# pulse_generator.net
KiCad netlist of a schematic drawn in EAGLE
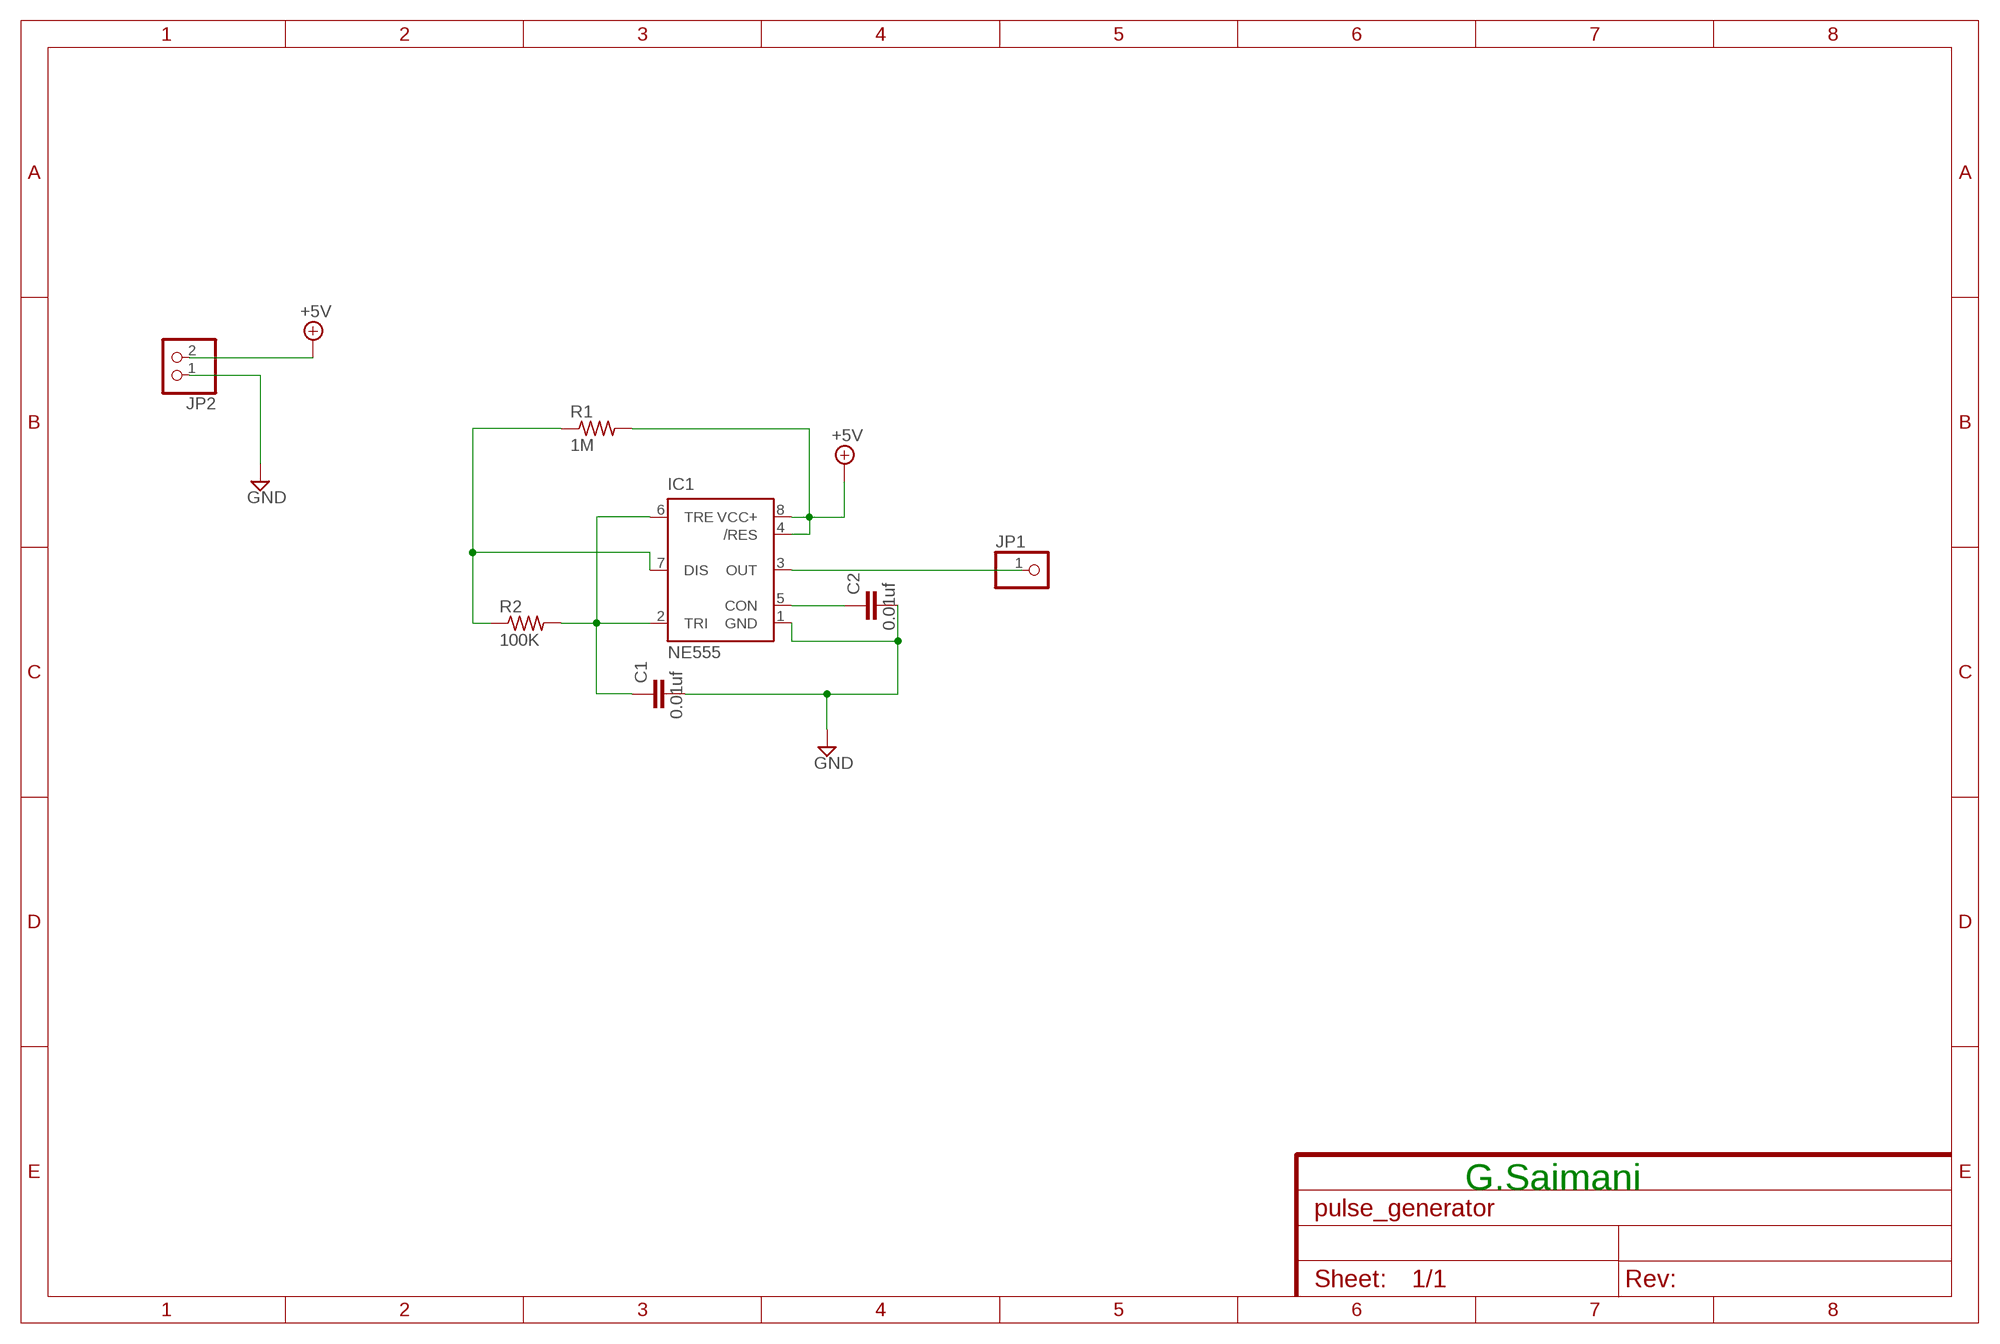
[diagram p0: schematic, sheet 1]

(export (version "E")
  (design (tool "Eeschema 10.0.6"))
  (components
    (comp (ref "C1")
      (value "0.01uf")
      (footprint "eagle-import:C050-024X044")
      (libsource (lib "eagle-import") (part "C-EU050-024X044"))
    )
    (comp (ref "C2")
      (value "0.01uf")
      (footprint "eagle-import:C050-024X044")
      (libsource (lib "eagle-import") (part "C-EU050-024X044"))
    )
    (comp (ref "IC1")
      (value "NE555")
      (footprint "eagle-import:DIL-08")
      (fields (field (name "MF") "Arrow Electronics") (field (name "MPN") "NE555N"))
      (libsource (lib "eagle-import") (part "NE555"))
    )
    (comp (ref "JP1")
      (value "PINHD-1X1")
      (footprint "eagle-import:1X01")
      (libsource (lib "eagle-import") (part "PINHD-1X1"))
    )
    (comp (ref "JP2")
      (value "PINHD-1X2")
      (footprint "eagle-import:1X02")
      (libsource (lib "eagle-import") (part "PINHD-1X2"))
    )
    (comp (ref "R1")
      (value "1M")
      (footprint "eagle-import:0204_7")
      (libsource (lib "eagle-import") (part "R-US_0204/7"))
    )
    (comp (ref "R2")
      (value "100K")
      (footprint "eagle-import:0204_7")
      (libsource (lib "eagle-import") (part "R-US_0204/7"))
    )
  )
  (nets
    (net (code "1") (name "+5V") (class "Default")
      (node (ref "IC1") (pin "4") (pinfunction "/RES_4") (pintype "input"))
      (node (ref "IC1") (pin "8") (pinfunction "VCC+_8") (pintype "power_in"))
      (node (ref "JP2") (pin "2") (pinfunction "2_2") (pintype "passive"))
      (node (ref "R1") (pin "2") (pinfunction "2_2") (pintype "passive"))
    )
    (net (code "2") (name "GND") (class "Default")
      (node (ref "C1") (pin "2") (pinfunction "2_2") (pintype "passive"))
      (node (ref "C2") (pin "2") (pinfunction "2_2") (pintype "passive"))
      (node (ref "IC1") (pin "1") (pinfunction "GND_1") (pintype "power_in"))
      (node (ref "JP2") (pin "1") (pinfunction "1_1") (pintype "passive"))
    )
    (net (code "3") (name "Net-(IC1-CON)") (class "Default")
      (node (ref "C2") (pin "1") (pinfunction "1_1") (pintype "passive"))
      (node (ref "IC1") (pin "5") (pinfunction "CON_5") (pintype "input"))
    )
    (net (code "4") (name "Net-(IC1-DIS)") (class "Default")
      (node (ref "IC1") (pin "7") (pinfunction "DIS_7") (pintype "input"))
      (node (ref "R1") (pin "1") (pinfunction "1_1") (pintype "passive"))
      (node (ref "R2") (pin "1") (pinfunction "1_1") (pintype "passive"))
    )
    (net (code "5") (name "Net-(IC1-OUT)") (class "Default")
      (node (ref "IC1") (pin "3") (pinfunction "OUT_3") (pintype "output"))
      (node (ref "JP1") (pin "1") (pinfunction "1_1") (pintype "passive"))
    )
    (net (code "6") (name "Net-(IC1-TRE)") (class "Default")
      (node (ref "C1") (pin "1") (pinfunction "1_1") (pintype "passive"))
      (node (ref "IC1") (pin "2") (pinfunction "TRI_2") (pintype "input"))
      (node (ref "IC1") (pin "6") (pinfunction "TRE_6") (pintype "input"))
      (node (ref "R2") (pin "2") (pinfunction "2_2") (pintype "passive"))
    )
  )
)
